# Sheet2.net
KiCad netlist of a schematic drawn in Altium Designer
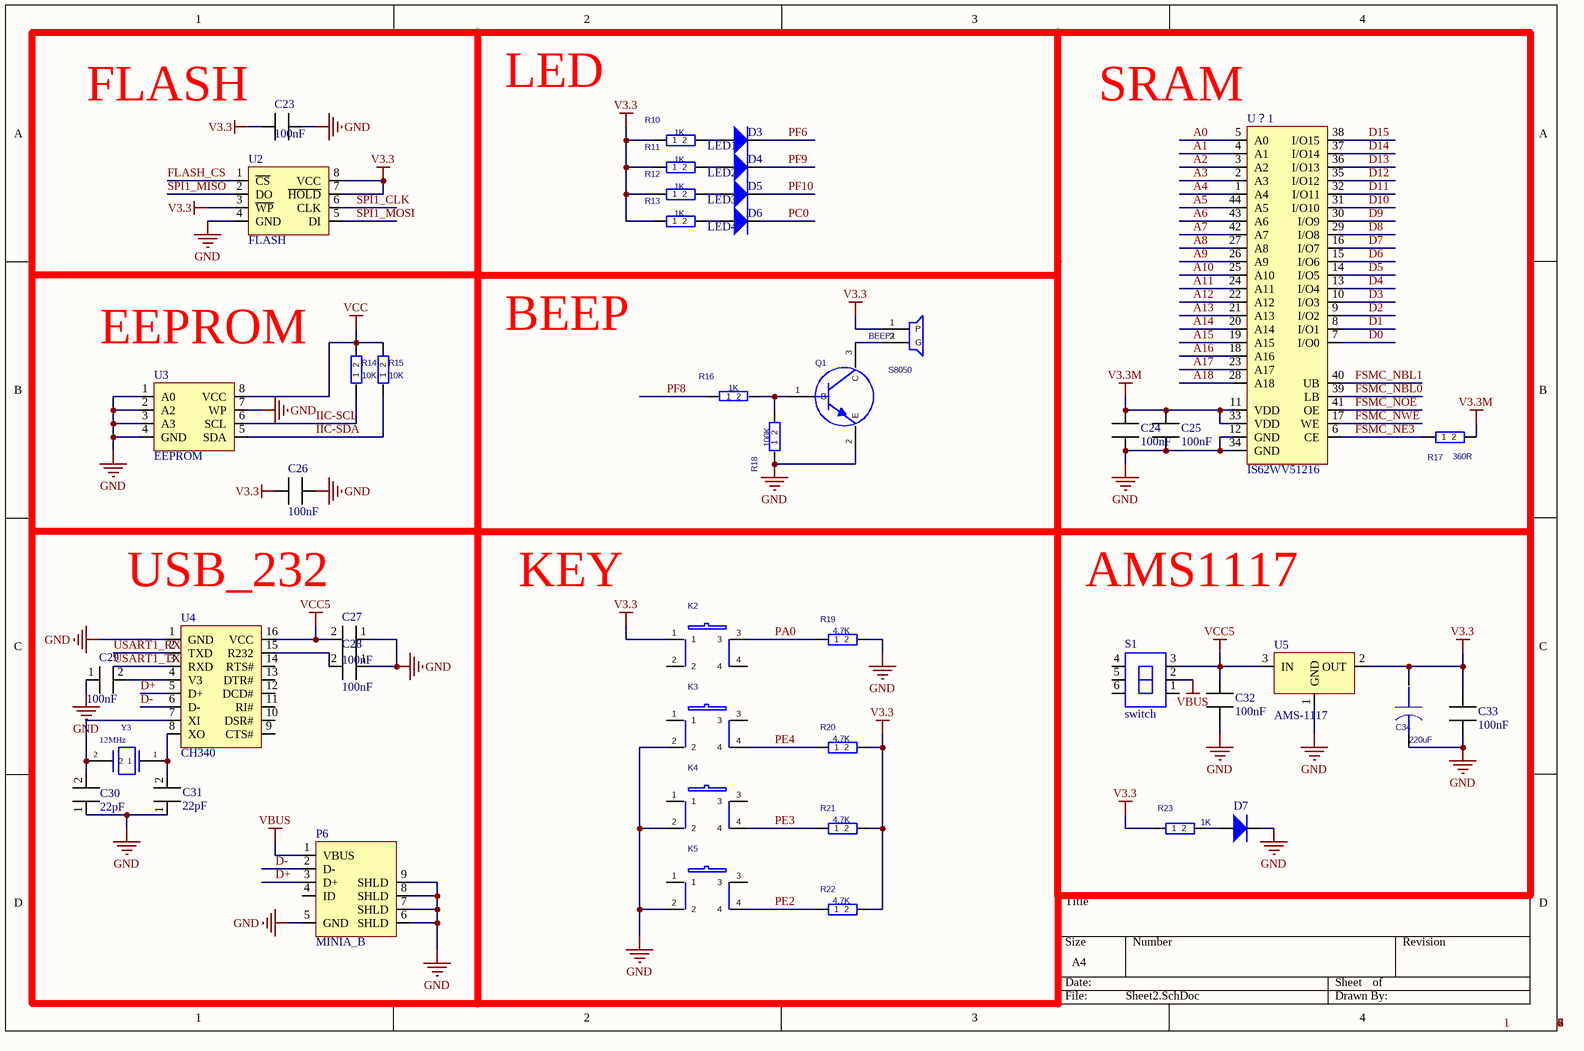
[diagram p0: Sheet2.SchDoc]

(export (version "E")
  (design (tool "Eeschema 10.0.6"))
  (components
    (comp (ref "BEEP1")
      (value "BEEP-9.5X5.5")
      (footprint "BEEP-9.5X5.5")
      (libsource (lib "F407ZGT6") (part "BEEP-9.5X5.5"))
    )
    (comp (ref "C23") (value "100nF") (footprint "CAP_0603_FIRE") (libsource (lib "") (part "CAP_1")))
    (comp (ref "C24") (value "100nF") (footprint "CAP_0603_FIRE") (libsource (lib "") (part "CAP_1")))
    (comp (ref "C25") (value "100nF") (footprint "CAP_0603_FIRE") (libsource (lib "") (part "CAP_1")))
    (comp (ref "C26") (value "100nF") (footprint "CAP_0603_FIRE") (libsource (lib "") (part "CAP_1")))
    (comp (ref "C27") (value "100nF") (footprint "CAP_0603_FIRE") (libsource (lib "F407ZGT6") (part "CAP")))
    (comp (ref "C28") (value "100nF") (footprint "CAP_0603_FIRE") (libsource (lib "F407ZGT6") (part "CAP")))
    (comp (ref "C29") (value "100nF") (footprint "CAP_0603_FIRE") (libsource (lib "F407ZGT6") (part "CAP")))
    (comp (ref "C30") (value "22pF") (footprint "CAP_0603_FIRE") (libsource (lib "F407ZGT6") (part "CAP")))
    (comp (ref "C31") (value "22pF") (footprint "CAP_0603_FIRE") (libsource (lib "F407ZGT6") (part "CAP")))
    (comp (ref "C32") (value "100nF") (footprint "CAP_0603_FIRE") (libsource (lib "") (part "CAP_1")))
    (comp (ref "C33") (value "100nF") (footprint "CAP_0603_FIRE") (libsource (lib "") (part "CAP_1")))
    (comp (ref "C34")
      (value "220uF")
      (footprint "CAP+_47UF_FIRE")
      (fields (field (name "Comment") "CAP+_47UF_FIRE"))
      (libsource (lib "F407ZGT6") (part "CAP+_47UF_FIRE"))
    )
    (comp (ref "D3") (value "LED1") (footprint "DIODE_SOP") (libsource (lib "F407ZGT6") (part "LED")))
    (comp (ref "D4") (value "LED2") (footprint "DIODE_SOP") (libsource (lib "F407ZGT6") (part "LED")))
    (comp (ref "D5") (value "LED3") (footprint "DIODE_SOP") (libsource (lib "F407ZGT6") (part "LED")))
    (comp (ref "D6") (value "LED4") (footprint "DIODE_SOP") (libsource (lib "F407ZGT6") (part "LED")))
    (comp (ref "D7") (value "~") (footprint "DIODE_SOP") (libsource (lib "F407ZGT6") (part "LED")))
    (comp (ref "K2") (value "KEY") (footprint "SW6.2/6.2-SMD") (libsource (lib "F407ZGT6") (part "KEY")))
    (comp (ref "K3") (value "KEY") (footprint "SW6.2/6.2-SMD") (libsource (lib "F407ZGT6") (part "KEY")))
    (comp (ref "K4") (value "KEY") (footprint "SW6.2/6.2-SMD") (libsource (lib "F407ZGT6") (part "KEY")))
    (comp (ref "K5") (value "KEY") (footprint "SW6.2/6.2-SMD") (libsource (lib "F407ZGT6") (part "KEY")))
    (comp (ref "P6") (value "MINIA_B") (footprint "USB-MINI") (libsource (lib "F407ZGT6") (part "MINIA_B")))
    (comp (ref "Q1")
      (value "S8050")
      (footprint "SOT-23")
      (description "NPN")
      (libsource (lib "F407ZGT6") (part "S8050"))
    )
    (comp (ref "R10")
      (value "1K")
      (footprint "RES_0603_FIRE")
      (description "0402")
      (fields (field (name "TOLERANCE") "+-5%") (field (name "Comment") "RES_1K_0603_FIRE"))
      (libsource (lib "F407ZGT6") (part "RES_1K_0603_FIRE"))
    )
    (comp (ref "R11")
      (value "1K")
      (footprint "RES_0603_FIRE")
      (description "0402")
      (fields (field (name "TOLERANCE") "+-5%") (field (name "Comment") "RES_1K_0603_FIRE"))
      (libsource (lib "F407ZGT6") (part "RES_1K_0603_FIRE"))
    )
    (comp (ref "R12")
      (value "1K")
      (footprint "RES_0603_FIRE")
      (description "0402")
      (fields (field (name "TOLERANCE") "+-5%") (field (name "Comment") "RES_1K_0603_FIRE"))
      (libsource (lib "F407ZGT6") (part "RES_1K_0603_FIRE"))
    )
    (comp (ref "R13")
      (value "1K")
      (footprint "RES_0603_FIRE")
      (description "0402")
      (fields (field (name "TOLERANCE") "+-5%") (field (name "Comment") "RES_1K_0603_FIRE"))
      (libsource (lib "F407ZGT6") (part "RES_1K_0603_FIRE"))
    )
    (comp (ref "R14")
      (value "10K")
      (footprint "RES_0603_FIRE")
      (description "SURFACE MOUNT RESISTOR 0.031 X 0.061 INCHES, 1/10W")
      (fields (field (name "Comment") "RES_10K_0603_FIRE"))
      (libsource (lib "F407ZGT6") (part "RES_10K_0603_FIRE"))
    )
    (comp (ref "R15")
      (value "10K")
      (footprint "RES_0603_FIRE")
      (description "SURFACE MOUNT RESISTOR 0.031 X 0.061 INCHES, 1/10W")
      (fields (field (name "Comment") "RES_10K_0603_FIRE"))
      (libsource (lib "F407ZGT6") (part "RES_10K_0603_FIRE"))
    )
    (comp (ref "R16")
      (value "1K")
      (footprint "RES_0603_FIRE")
      (description "0402")
      (fields (field (name "TOLERANCE") "+-5%") (field (name "Comment") "RES_100R_0603_FIRE"))
      (libsource (lib "F407ZGT6") (part "RES_100R_0603_FIRE"))
    )
    (comp (ref "R17")
      (value "360R")
      (footprint "RES_0603_FIRE")
      (description "0402")
      (fields (field (name "TOLERANCE") "+-5%") (field (name "Comment") "RES_1K_0603_FIRE"))
      (libsource (lib "F407ZGT6") (part "RES_1K_0603_FIRE"))
    )
    (comp (ref "R18")
      (value "100K")
      (footprint "RES_0603_FIRE")
      (description "0402")
      (fields (field (name "TOLERANCE") "+-5%") (field (name "Comment") "RES_1K_0603_FIRE"))
      (libsource (lib "F407ZGT6") (part "RES_1K_0603_FIRE"))
    )
    (comp (ref "R19")
      (value "4.7K")
      (footprint "RES_0603_FIRE")
      (description "0402")
      (fields (field (name "TOLERANCE") "+-5%") (field (name "Comment") "RES_4K7_0603_FIRE"))
      (libsource (lib "F407ZGT6") (part "RES_4K7_0603_FIRE"))
    )
    (comp (ref "R20")
      (value "4.7K")
      (footprint "RES_0603_FIRE")
      (description "0402")
      (fields (field (name "TOLERANCE") "+-5%") (field (name "Comment") "RES_4K7_0603_FIRE"))
      (libsource (lib "F407ZGT6") (part "RES_4K7_0603_FIRE"))
    )
    (comp (ref "R21")
      (value "4.7K")
      (footprint "RES_0603_FIRE")
      (description "0402")
      (fields (field (name "TOLERANCE") "+-5%") (field (name "Comment") "RES_4K7_0603_FIRE"))
      (libsource (lib "F407ZGT6") (part "RES_4K7_0603_FIRE"))
    )
    (comp (ref "R22")
      (value "4.7K")
      (footprint "RES_0603_FIRE")
      (description "0402")
      (fields (field (name "TOLERANCE") "+-5%") (field (name "Comment") "RES_4K7_0603_FIRE"))
      (libsource (lib "F407ZGT6") (part "RES_4K7_0603_FIRE"))
    )
    (comp (ref "R23")
      (value "1K")
      (footprint "RES_0603_FIRE")
      (description "0402")
      (fields (field (name "TOLERANCE") "+-5%") (field (name "Comment") "RES_1K_0603_FIRE"))
      (libsource (lib "F407ZGT6") (part "RES_1K_0603_FIRE"))
    )
    (comp (ref "S1") (value "switch") (footprint "switch") (libsource (lib "F407ZGT6") (part "switch")))
    (comp (ref "U2") (value "FLASH") (footprint "SOP8A") (libsource (lib "F407ZGT6") (part "FLASH")))
    (comp (ref "U3") (value "EEPROM") (footprint "SOP8") (libsource (lib "F407ZGT6") (part "EEPROM")))
    (comp (ref "U4") (value "CH340") (footprint "SOP16") (libsource (lib "F407ZGT6") (part "CH340")))
    (comp (ref "U5")
      (value "AMS-1117")
      (footprint "AMS-1117-3.3")
      (libsource (lib "F407ZGT6") (part "AMS-1117"))
    )
    (comp (ref "U？1")
      (value "IS62WV51216")
      (footprint "IS62WV51216")
      (libsource (lib "F407ZGT6") (part "IS62WV51216"))
    )
    (comp (ref "Y3")
      (value "12MHz")
      (footprint "XTAL_SMD")
      (fields (field (name "Comment") "XTAL_12M"))
      (libsource (lib "F407ZGT6") (part "XTAL_12M"))
    )
  )
  (nets
    (net (code "3") (name "/A0") (class "Default")
      (node (ref "U？1") (pin "5") (pinfunction "A0_5") (pintype "passive"))
    )
    (net (code "4") (name "/A1") (class "Default")
      (node (ref "U？1") (pin "4") (pinfunction "A1_4") (pintype "passive"))
    )
    (net (code "5") (name "/A2") (class "Default")
      (node (ref "U？1") (pin "3") (pinfunction "A2_3") (pintype "passive"))
    )
    (net (code "6") (name "/A3") (class "Default")
      (node (ref "U？1") (pin "2") (pinfunction "A3_2") (pintype "passive"))
    )
    (net (code "7") (name "/A4") (class "Default")
      (node (ref "U？1") (pin "1") (pinfunction "A4_1") (pintype "passive"))
    )
    (net (code "8") (name "/A5") (class "Default")
      (node (ref "U？1") (pin "44") (pinfunction "A5_44") (pintype "passive"))
    )
    (net (code "9") (name "/A6") (class "Default")
      (node (ref "U？1") (pin "43") (pinfunction "A6_43") (pintype "passive"))
    )
    (net (code "10") (name "/A7") (class "Default")
      (node (ref "U？1") (pin "42") (pinfunction "A7_42") (pintype "passive"))
    )
    (net (code "11") (name "/A8") (class "Default")
      (node (ref "U？1") (pin "27") (pinfunction "A8_27") (pintype "passive"))
    )
    (net (code "12") (name "/A9") (class "Default")
      (node (ref "U？1") (pin "26") (pinfunction "A9_26") (pintype "passive"))
    )
    (net (code "13") (name "/A10") (class "Default")
      (node (ref "U？1") (pin "25") (pinfunction "A10_25") (pintype "passive"))
    )
    (net (code "14") (name "/A11") (class "Default")
      (node (ref "U？1") (pin "24") (pinfunction "A11_24") (pintype "passive"))
    )
    (net (code "15") (name "/A12") (class "Default")
      (node (ref "U？1") (pin "22") (pinfunction "A12_22") (pintype "passive"))
    )
    (net (code "16") (name "/A13") (class "Default")
      (node (ref "U？1") (pin "21") (pinfunction "A13_21") (pintype "passive"))
    )
    (net (code "17") (name "/A14") (class "Default")
      (node (ref "U？1") (pin "20") (pinfunction "A14_20") (pintype "passive"))
    )
    (net (code "18") (name "/A15") (class "Default")
      (node (ref "U？1") (pin "19") (pinfunction "A15_19") (pintype "passive"))
    )
    (net (code "19") (name "/A16") (class "Default")
      (node (ref "U？1") (pin "18") (pinfunction "A16_18") (pintype "passive"))
    )
    (net (code "20") (name "/A17") (class "Default")
      (node (ref "U？1") (pin "23") (pinfunction "A17_23") (pintype "passive"))
    )
    (net (code "21") (name "/A18") (class "Default")
      (node (ref "U？1") (pin "28") (pinfunction "A18_28") (pintype "passive"))
    )
    (net (code "22") (name "/D+") (class "Default")
      (node (ref "P6") (pin "3") (pinfunction "D+_3") (pintype "passive"))
      (node (ref "U4") (pin "5") (pinfunction "D+_5") (pintype "passive"))
    )
    (net (code "23") (name "/D-") (class "Default")
      (node (ref "P6") (pin "2") (pinfunction "D-_2") (pintype "passive"))
      (node (ref "U4") (pin "6") (pinfunction "D-_6") (pintype "passive"))
    )
    (net (code "24") (name "/D0") (class "Default")
      (node (ref "U？1") (pin "7") (pinfunction "I/O0_7") (pintype "passive"))
    )
    (net (code "25") (name "/D1") (class "Default")
      (node (ref "U？1") (pin "8") (pinfunction "I/O1_8") (pintype "passive"))
    )
    (net (code "26") (name "/D2") (class "Default")
      (node (ref "U？1") (pin "9") (pinfunction "I/O2_9") (pintype "passive"))
    )
    (net (code "27") (name "/D3") (class "Default")
      (node (ref "U？1") (pin "10") (pinfunction "I/O3_10") (pintype "passive"))
    )
    (net (code "28") (name "/D4") (class "Default")
      (node (ref "U？1") (pin "13") (pinfunction "I/O4_13") (pintype "passive"))
    )
    (net (code "29") (name "/D5") (class "Default")
      (node (ref "U？1") (pin "14") (pinfunction "I/O5_14") (pintype "passive"))
    )
    (net (code "30") (name "/D6") (class "Default")
      (node (ref "U？1") (pin "15") (pinfunction "I/O6_15") (pintype "passive"))
    )
    (net (code "31") (name "/D7") (class "Default")
      (node (ref "U？1") (pin "16") (pinfunction "I/O7_16") (pintype "passive"))
    )
    (net (code "32") (name "/D8") (class "Default")
      (node (ref "U？1") (pin "29") (pinfunction "I/O8_29") (pintype "passive"))
    )
    (net (code "33") (name "/D9") (class "Default")
      (node (ref "U？1") (pin "30") (pinfunction "I/O9_30") (pintype "passive"))
    )
    (net (code "34") (name "/D10") (class "Default")
      (node (ref "U？1") (pin "31") (pinfunction "I/O10_31") (pintype "passive"))
    )
    (net (code "35") (name "/D11") (class "Default")
      (node (ref "U？1") (pin "32") (pinfunction "I/O11_32") (pintype "passive"))
    )
    (net (code "36") (name "/D12") (class "Default")
      (node (ref "U？1") (pin "35") (pinfunction "I/O12_35") (pintype "passive"))
    )
    (net (code "37") (name "/D13") (class "Default")
      (node (ref "U？1") (pin "36") (pinfunction "I/O13_36") (pintype "passive"))
    )
    (net (code "38") (name "/D14") (class "Default")
      (node (ref "U？1") (pin "37") (pinfunction "I/O14_37") (pintype "passive"))
    )
    (net (code "39") (name "/D15") (class "Default")
      (node (ref "U？1") (pin "38") (pinfunction "I/O15_38") (pintype "passive"))
    )
    (net (code "40") (name "/FLASH_CS") (class "Default")
      (node (ref "U2") (pin "1") (pinfunction "~{CS}_1") (pintype "passive"))
    )
    (net (code "41") (name "/FSMC_NBL0") (class "Default")
      (node (ref "U？1") (pin "39") (pinfunction "LB_39") (pintype "passive"))
    )
    (net (code "42") (name "/FSMC_NBL1") (class "Default")
      (node (ref "U？1") (pin "40") (pinfunction "UB_40") (pintype "passive"))
    )
    (net (code "43") (name "/FSMC_NE3") (class "Default")
      (node (ref "R17") (pin "1") (pinfunction "1_1") (pintype "passive"))
      (node (ref "U？1") (pin "6") (pinfunction "CE_6") (pintype "passive"))
    )
    (net (code "44") (name "/FSMC_NOE") (class "Default")
      (node (ref "U？1") (pin "41") (pinfunction "OE_41") (pintype "passive"))
    )
    (net (code "45") (name "/FSMC_NWE") (class "Default")
      (node (ref "U？1") (pin "17") (pinfunction "WE_17") (pintype "passive"))
    )
    (net (code "46") (name "/IIC-SCL") (class "Default")
      (node (ref "R14") (pin "1") (pinfunction "1_1") (pintype "passive"))
      (node (ref "U3") (pin "6") (pinfunction "SCL_6") (pintype "passive"))
    )
    (net (code "47") (name "/IIC-SDA") (class "Default")
      (node (ref "R15") (pin "1") (pinfunction "1_1") (pintype "passive"))
      (node (ref "U3") (pin "5") (pinfunction "SDA_5") (pintype "passive"))
    )
    (net (code "48") (name "/PA0") (class "Default")
      (node (ref "K2") (pin "3") (pinfunction "3_3") (pintype "passive"))
      (node (ref "R19") (pin "1") (pinfunction "1_1") (pintype "passive"))
    )
    (net (code "49") (name "/PC0") (class "Default")
      (node (ref "D6") (pin "2") (pinfunction "2_2") (pintype "passive"))
    )
    (net (code "50") (name "/PE2") (class "Default")
      (node (ref "K5") (pin "4") (pinfunction "4_4") (pintype "passive"))
      (node (ref "R22") (pin "1") (pinfunction "1_1") (pintype "passive"))
    )
    (net (code "51") (name "/PE3") (class "Default")
      (node (ref "K4") (pin "4") (pinfunction "4_4") (pintype "passive"))
      (node (ref "R21") (pin "1") (pinfunction "1_1") (pintype "passive"))
    )
    (net (code "52") (name "/PE4") (class "Default")
      (node (ref "K3") (pin "4") (pinfunction "4_4") (pintype "passive"))
      (node (ref "R20") (pin "1") (pinfunction "1_1") (pintype "passive"))
    )
    (net (code "53") (name "/PF6") (class "Default")
      (node (ref "D3") (pin "2") (pinfunction "2_2") (pintype "passive"))
    )
    (net (code "54") (name "/PF8") (class "Default")
      (node (ref "R16") (pin "1") (pinfunction "1_1") (pintype "passive"))
    )
    (net (code "55") (name "/PF9") (class "Default")
      (node (ref "D4") (pin "2") (pinfunction "2_2") (pintype "passive"))
    )
    (net (code "56") (name "/PF10") (class "Default")
      (node (ref "D5") (pin "2") (pinfunction "2_2") (pintype "passive"))
    )
    (net (code "57") (name "/SPI1_CLK") (class "Default")
      (node (ref "U2") (pin "6") (pinfunction "CLK_6") (pintype "passive"))
    )
    (net (code "58") (name "/SPI1_MISO") (class "Default")
      (node (ref "U2") (pin "2") (pinfunction "DO_2") (pintype "passive"))
    )
    (net (code "59") (name "/SPI1_MOSI") (class "Default")
      (node (ref "U2") (pin "5") (pinfunction "DI_5") (pintype "passive"))
    )
    (net (code "60") (name "/USART1_RX") (class "Default")
      (node (ref "U4") (pin "2") (pinfunction "TXD_2") (pintype "passive"))
    )
    (net (code "61") (name "/USART1_TX") (class "Default")
      (node (ref "U4") (pin "3") (pinfunction "RXD_3") (pintype "passive"))
    )
    (net (code "62") (name "GND") (class "Default")
      (node (ref "C23") (pin "1") (pinfunction "1_1") (pintype "passive"))
      (node (ref "C24") (pin "1") (pinfunction "1_1") (pintype "passive"))
      (node (ref "C25") (pin "1") (pinfunction "1_1") (pintype "passive"))
      (node (ref "C26") (pin "1") (pinfunction "1_1") (pintype "passive"))
      (node (ref "C27") (pin "1") (pinfunction "1_1") (pintype "passive"))
      (node (ref "C28") (pin "1") (pinfunction "1_1") (pintype "passive"))
      (node (ref "C29") (pin "1") (pinfunction "1_1") (pintype "passive"))
      (node (ref "C30") (pin "1") (pinfunction "1_1") (pintype "passive"))
      (node (ref "C31") (pin "1") (pinfunction "1_1") (pintype "passive"))
      (node (ref "C32") (pin "1") (pinfunction "1_1") (pintype "passive"))
      (node (ref "C33") (pin "1") (pinfunction "1_1") (pintype "passive"))
      (node (ref "C34") (pin "2") (pinfunction "2_2") (pintype "passive"))
      (node (ref "D7") (pin "2") (pinfunction "2_2") (pintype "passive"))
      (node (ref "K3") (pin "2") (pinfunction "2_2") (pintype "passive"))
      (node (ref "K4") (pin "2") (pinfunction "2_2") (pintype "passive"))
      (node (ref "K5") (pin "2") (pinfunction "2_2") (pintype "passive"))
      (node (ref "P6") (pin "5") (pinfunction "GND_5") (pintype "passive"))
      (node (ref "P6") (pin "6") (pinfunction "SHLD_6") (pintype "passive"))
      (node (ref "P6") (pin "7") (pinfunction "SHLD_7") (pintype "passive"))
      (node (ref "P6") (pin "8") (pinfunction "SHLD_8") (pintype "passive"))
      (node (ref "P6") (pin "9") (pinfunction "SHLD_9") (pintype "passive"))
      (node (ref "Q1") (pin "2") (pinfunction "E_2") (pintype "passive"))
      (node (ref "R18") (pin "1") (pinfunction "1_1") (pintype "passive"))
      (node (ref "R19") (pin "2") (pinfunction "2_2") (pintype "passive"))
      (node (ref "U2") (pin "4") (pinfunction "GND_4") (pintype "passive"))
      (node (ref "U3") (pin "1") (pinfunction "A0_1") (pintype "passive"))
      (node (ref "U3") (pin "2") (pinfunction "A2_2") (pintype "passive"))
      (node (ref "U3") (pin "3") (pinfunction "A3_3") (pintype "passive"))
      (node (ref "U3") (pin "4") (pinfunction "GND_4") (pintype "passive"))
      (node (ref "U3") (pin "7") (pinfunction "WP_7") (pintype "passive"))
      (node (ref "U4") (pin "1") (pinfunction "GND_1") (pintype "passive"))
      (node (ref "U5") (pin "1") (pinfunction "GND_1") (pintype "passive"))
      (node (ref "U？1") (pin "12") (pinfunction "GND_12") (pintype "passive"))
      (node (ref "U？1") (pin "34") (pinfunction "GND_34") (pintype "passive"))
    )
    (net (code "63") (name "Net-(BEEP1-G)") (class "Default")
      (node (ref "BEEP1") (pin "2") (pinfunction "G_2") (pintype "passive"))
      (node (ref "Q1") (pin "3") (pinfunction "C_3") (pintype "passive"))
    )
    (net (code "64") (name "Net-(D3-Pad1)") (class "Default")
      (node (ref "D3") (pin "1") (pinfunction "1_1") (pintype "passive"))
      (node (ref "R10") (pin "2") (pinfunction "2_2") (pintype "passive"))
    )
    (net (code "65") (name "Net-(D4-Pad1)") (class "Default")
      (node (ref "D4") (pin "1") (pinfunction "1_1") (pintype "passive"))
      (node (ref "R11") (pin "2") (pinfunction "2_2") (pintype "passive"))
    )
    (net (code "66") (name "Net-(D5-Pad1)") (class "Default")
      (node (ref "D5") (pin "1") (pinfunction "1_1") (pintype "passive"))
      (node (ref "R12") (pin "2") (pinfunction "2_2") (pintype "passive"))
    )
    (net (code "67") (name "Net-(D6-Pad1)") (class "Default")
      (node (ref "D6") (pin "1") (pinfunction "1_1") (pintype "passive"))
      (node (ref "R13") (pin "2") (pinfunction "2_2") (pintype "passive"))
    )
    (net (code "68") (name "Net-(D7-Pad1)") (class "Default")
      (node (ref "D7") (pin "1") (pinfunction "1_1") (pintype "passive"))
      (node (ref "R23") (pin "2") (pinfunction "2_2") (pintype "passive"))
    )
    (net (code "69") (name "Net-(Q1-B)") (class "Default")
      (node (ref "Q1") (pin "1") (pinfunction "B_1") (pintype "passive"))
      (node (ref "R16") (pin "2") (pinfunction "2_2") (pintype "passive"))
      (node (ref "R18") (pin "2") (pinfunction "2_2") (pintype "passive"))
    )
    (net (code "70") (name "Net-(U4-R232)") (class "Default")
      (node (ref "C28") (pin "2") (pinfunction "2_2") (pintype "passive"))
      (node (ref "U4") (pin "15") (pinfunction "R232_15") (pintype "passive"))
    )
    (net (code "71") (name "Net-(U4-V3)") (class "Default")
      (node (ref "C29") (pin "2") (pinfunction "2_2") (pintype "passive"))
      (node (ref "U4") (pin "4") (pinfunction "V3_4") (pintype "passive"))
    )
    (net (code "72") (name "Net-(U4-XI)") (class "Default")
      (node (ref "C30") (pin "2") (pinfunction "2_2") (pintype "passive"))
      (node (ref "U4") (pin "7") (pinfunction "XI_7") (pintype "passive"))
      (node (ref "Y3") (pin "2") (pinfunction "2_2") (pintype "passive"))
    )
    (net (code "73") (name "Net-(U4-XO)") (class "Default")
      (node (ref "C31") (pin "2") (pinfunction "2_2") (pintype "passive"))
      (node (ref "U4") (pin "8") (pinfunction "XO_8") (pintype "passive"))
      (node (ref "Y3") (pin "1") (pinfunction "1_1") (pintype "passive"))
    )
    (net (code "74") (name "V3.3") (class "Default")
      (node (ref "BEEP1") (pin "1") (pinfunction "P_1") (pintype "passive"))
      (node (ref "C23") (pin "2") (pinfunction "2_2") (pintype "passive"))
      (node (ref "C26") (pin "2") (pinfunction "2_2") (pintype "passive"))
      (node (ref "C33") (pin "2") (pinfunction "2_2") (pintype "passive"))
      (node (ref "C34") (pin "1") (pinfunction "1_1") (pintype "passive"))
      (node (ref "K2") (pin "1") (pinfunction "1_1") (pintype "passive"))
      (node (ref "R10") (pin "1") (pinfunction "1_1") (pintype "passive"))
      (node (ref "R11") (pin "1") (pinfunction "1_1") (pintype "passive"))
      (node (ref "R12") (pin "1") (pinfunction "1_1") (pintype "passive"))
      (node (ref "R13") (pin "1") (pinfunction "1_1") (pintype "passive"))
      (node (ref "R20") (pin "2") (pinfunction "2_2") (pintype "passive"))
      (node (ref "R21") (pin "2") (pinfunction "2_2") (pintype "passive"))
      (node (ref "R22") (pin "2") (pinfunction "2_2") (pintype "passive"))
      (node (ref "R23") (pin "1") (pinfunction "1_1") (pintype "passive"))
      (node (ref "U2") (pin "3") (pinfunction "~{WP}_3") (pintype "passive"))
      (node (ref "U2") (pin "7") (pinfunction "~{HOLD}_7") (pintype "passive"))
      (node (ref "U2") (pin "8") (pinfunction "VCC_8") (pintype "passive"))
      (node (ref "U5") (pin "2") (pinfunction "OUT_2") (pintype "passive"))
    )
    (net (code "75") (name "V3.3M") (class "Default")
      (node (ref "C24") (pin "2") (pinfunction "2_2") (pintype "passive"))
      (node (ref "C25") (pin "2") (pinfunction "2_2") (pintype "passive"))
      (node (ref "R17") (pin "2") (pinfunction "2_2") (pintype "passive"))
      (node (ref "U？1") (pin "11") (pinfunction "VDD_11") (pintype "passive"))
      (node (ref "U？1") (pin "33") (pinfunction "VDD_33") (pintype "passive"))
    )
    (net (code "76") (name "VBUS") (class "Default")
      (node (ref "P6") (pin "1") (pinfunction "VBUS_1") (pintype "passive"))
      (node (ref "S1") (pin "2") (pinfunction "2_2") (pintype "passive"))
    )
    (net (code "77") (name "VCC") (class "Default")
      (node (ref "R14") (pin "2") (pinfunction "2_2") (pintype "passive"))
      (node (ref "R15") (pin "2") (pinfunction "2_2") (pintype "passive"))
      (node (ref "U3") (pin "8") (pinfunction "VCC_8") (pintype "passive"))
    )
    (net (code "78") (name "VCC5") (class "Default")
      (node (ref "C27") (pin "2") (pinfunction "2_2") (pintype "passive"))
      (node (ref "C32") (pin "2") (pinfunction "2_2") (pintype "passive"))
      (node (ref "S1") (pin "3") (pinfunction "3_3") (pintype "passive"))
      (node (ref "U4") (pin "16") (pinfunction "VCC_16") (pintype "passive"))
      (node (ref "U5") (pin "3") (pinfunction "IN_3") (pintype "passive"))
    )
    (net (code "79") (name "unconnected-(K2-Pad2)") (class "Default")
      (node (ref "K2") (pin "2") (pinfunction "2_2") (pintype "passive"))
    )
    (net (code "80") (name "unconnected-(K2-Pad4)") (class "Default")
      (node (ref "K2") (pin "4") (pinfunction "4_4") (pintype "passive"))
    )
    (net (code "81") (name "unconnected-(K3-Pad1)") (class "Default")
      (node (ref "K3") (pin "1") (pinfunction "1_1") (pintype "passive"))
    )
    (net (code "82") (name "unconnected-(K3-Pad3)") (class "Default")
      (node (ref "K3") (pin "3") (pinfunction "3_3") (pintype "passive"))
    )
    (net (code "83") (name "unconnected-(K4-Pad1)") (class "Default")
      (node (ref "K4") (pin "1") (pinfunction "1_1") (pintype "passive"))
    )
    (net (code "84") (name "unconnected-(K4-Pad3)") (class "Default")
      (node (ref "K4") (pin "3") (pinfunction "3_3") (pintype "passive"))
    )
    (net (code "85") (name "unconnected-(K5-Pad1)") (class "Default")
      (node (ref "K5") (pin "1") (pinfunction "1_1") (pintype "passive"))
    )
    (net (code "86") (name "unconnected-(K5-Pad3)") (class "Default")
      (node (ref "K5") (pin "3") (pinfunction "3_3") (pintype "passive"))
    )
    (net (code "87") (name "unconnected-(P6-ID-Pad4)") (class "Default")
      (node (ref "P6") (pin "4") (pinfunction "ID_4") (pintype "passive"))
    )
    (net (code "88") (name "unconnected-(S1-Pad1)") (class "Default")
      (node (ref "S1") (pin "1") (pinfunction "1_1") (pintype "passive"))
    )
    (net (code "89") (name "unconnected-(S1-Pad4)") (class "Default")
      (node (ref "S1") (pin "4") (pinfunction "4_4") (pintype "passive"))
    )
    (net (code "90") (name "unconnected-(S1-Pad5)") (class "Default")
      (node (ref "S1") (pin "5") (pinfunction "5_5") (pintype "passive"))
    )
    (net (code "91") (name "unconnected-(S1-Pad6)") (class "Default")
      (node (ref "S1") (pin "6") (pinfunction "6_6") (pintype "passive"))
    )
    (net (code "92") (name "unconnected-(U4-CTS#-Pad9)") (class "Default")
      (node (ref "U4") (pin "9") (pinfunction "CTS#_9") (pintype "passive"))
    )
    (net (code "93") (name "unconnected-(U4-DCD#-Pad12)") (class "Default")
      (node (ref "U4") (pin "12") (pinfunction "DCD#_12") (pintype "passive"))
    )
    (net (code "94") (name "unconnected-(U4-DSR#-Pad10)") (class "Default")
      (node (ref "U4") (pin "10") (pinfunction "DSR#_10") (pintype "passive"))
    )
    (net (code "95") (name "unconnected-(U4-DTR#-Pad13)") (class "Default")
      (node (ref "U4") (pin "13") (pinfunction "DTR#_13") (pintype "passive"))
    )
    (net (code "96") (name "unconnected-(U4-RI#-Pad11)") (class "Default")
      (node (ref "U4") (pin "11") (pinfunction "RI#_11") (pintype "passive"))
    )
    (net (code "97") (name "unconnected-(U4-RTS#-Pad14)") (class "Default")
      (node (ref "U4") (pin "14") (pinfunction "RTS#_14") (pintype "passive"))
    )
  )
)
